# ADC.net
KiCad netlist of a schematic drawn in Altium Designer
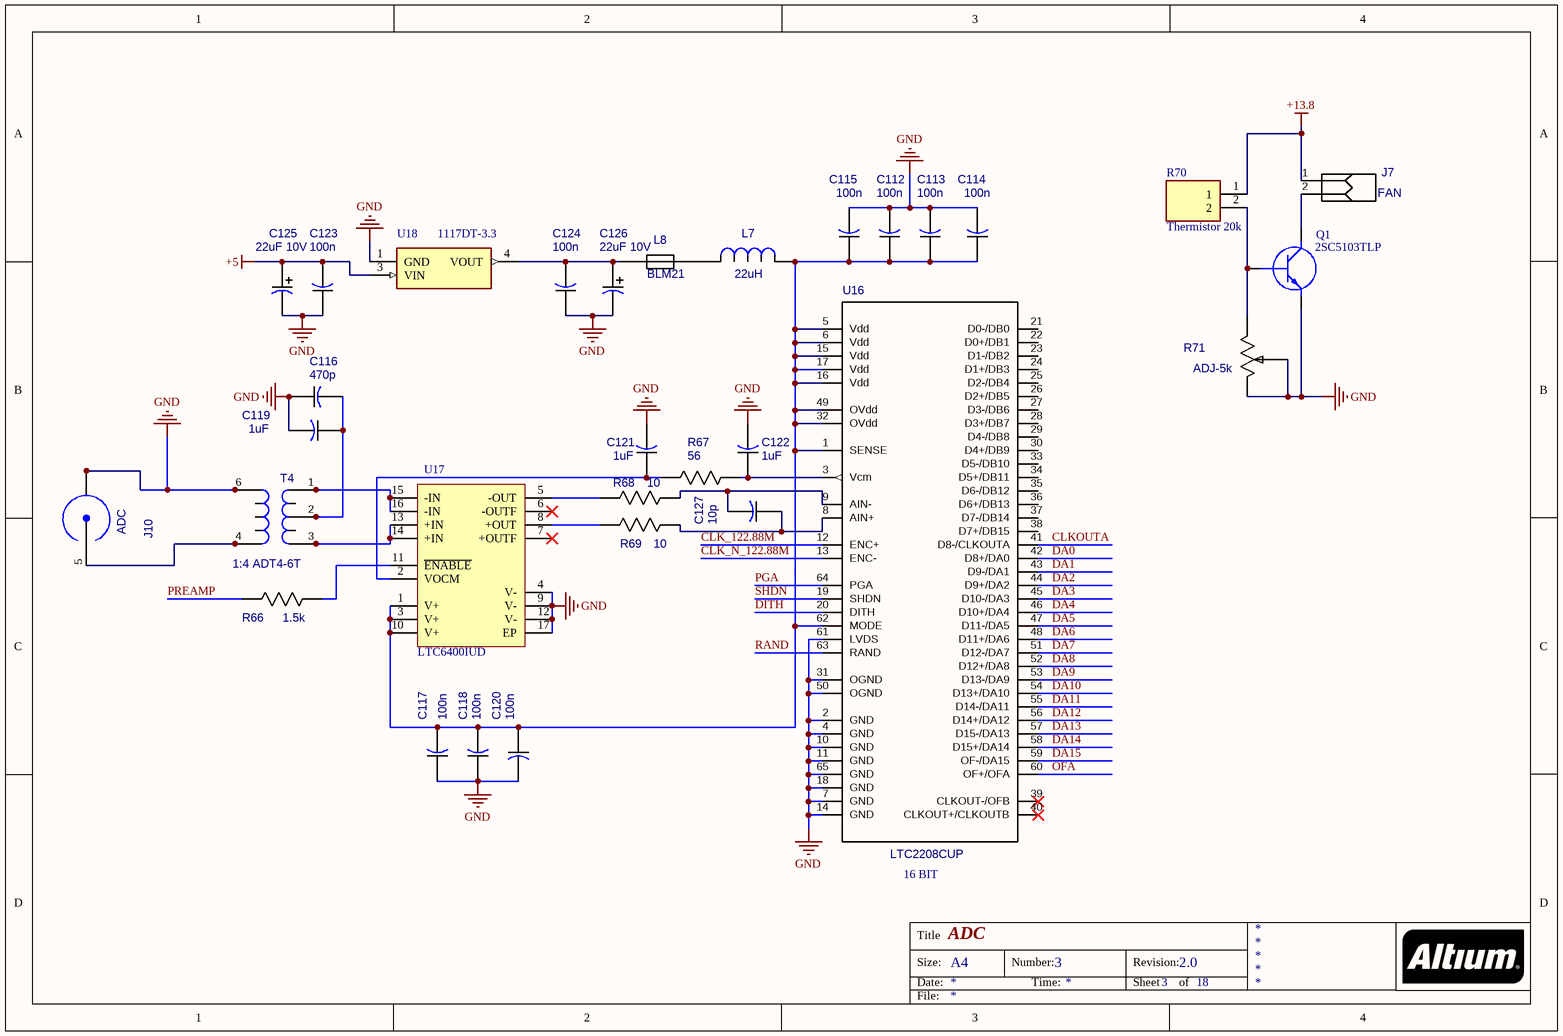
[diagram p0: ADC.SchDoc]

(export (version "E")
  (design (tool "Eeschema 10.0.6"))
  (components
    (comp (ref "C112")
      (value "100n")
      (footprint "CAP_0805")
      (description "CAP_0805")
      (libsource (lib "*") (part "CAP_0805"))
    )
    (comp (ref "C113")
      (value "100n")
      (footprint "CAP_0805")
      (description "CAP_0805")
      (libsource (lib "*") (part "CAP_0805"))
    )
    (comp (ref "C114")
      (value "100n")
      (footprint "CAP_0805")
      (description "CAP_0805")
      (libsource (lib "*") (part "CAP_0805"))
    )
    (comp (ref "C115")
      (value "100n")
      (footprint "CAP_0805")
      (description "CAP_0805")
      (libsource (lib "*") (part "CAP_0805"))
    )
    (comp (ref "C116")
      (value "470p")
      (footprint "CAP_0805")
      (description "CAP_0805")
      (libsource (lib "*") (part "CAP_0805"))
    )
    (comp (ref "C117")
      (value "100n")
      (footprint "CAP_0805")
      (description "CAP_0805")
      (libsource (lib "*") (part "CAP_0805"))
    )
    (comp (ref "C118")
      (value "100n")
      (footprint "CAP_0805")
      (description "CAP_0805")
      (libsource (lib "*") (part "CAP_0805"))
    )
    (comp (ref "C119")
      (value "1uF")
      (footprint "CAP_0805")
      (description "CAP_0805")
      (libsource (lib "*") (part "CAP_0805"))
    )
    (comp (ref "C120")
      (value "100n")
      (footprint "CAP_0805")
      (description "CAP_0805")
      (libsource (lib "*") (part "CAP_0805"))
    )
    (comp (ref "C121")
      (value "1uF")
      (footprint "CAP_0805")
      (description "CAP_0805")
      (libsource (lib "*") (part "CAP_0805"))
    )
    (comp (ref "C122")
      (value "1uF")
      (footprint "CAP_0805")
      (description "CAP_0805")
      (libsource (lib "*") (part "CAP_0805"))
    )
    (comp (ref "C123")
      (value "100n")
      (footprint "CAP_0805")
      (description "CAP_0805")
      (libsource (lib "*") (part "CAP_0805"))
    )
    (comp (ref "C124")
      (value "100n")
      (footprint "CAP_0805")
      (description "CAP_0805")
      (libsource (lib "*") (part "CAP_0805"))
    )
    (comp (ref "C125")
      (value "22uF 10V")
      (footprint "CAPAE_4.3x4.3h5.4")
      (description "CAPAE_4.3x4.3h5.4")
      (libsource (lib "MOTHERBOARD") (part "CAPAE_4.3x4.3h5.4"))
    )
    (comp (ref "C126")
      (value "22uF 10V")
      (footprint "CAPAE_4.3x4.3h5.4")
      (description "CAPAE_4.3x4.3h5.4")
      (libsource (lib "MOTHERBOARD") (part "CAPAE_4.3x4.3h5.4"))
    )
    (comp (ref "C127")
      (value "10p")
      (footprint "CAP_0805")
      (description "CAP_0805")
      (libsource (lib "*") (part "CAP_0805"))
    )
    (comp (ref "J7")
      (value "FAN")
      (footprint "51022-0200")
      (description "51022-0200")
      (libsource (lib "*") (part "51022-0200"))
    )
    (comp (ref "J10")
      (value "ADC")
      (footprint "31-5431")
      (description "SMA")
      (libsource (lib "RF-UNIT_1") (part "31-5431"))
    )
    (comp (ref "L7")
      (value "22uH")
      (footprint "IND_7x7")
      (description "IND_1206")
      (libsource (lib "*") (part "IND_1206"))
    )
    (comp (ref "L8")
      (value "BLM21")
      (footprint "CAP_0805")
      (libsource (lib "MOTHERBOARD_1") (part "IND_FERRITE_BEAD"))
    )
    (comp (ref "Q1")
      (value "2SC5103TLP")
      (footprint "SamacSys:2SC5103TLQ")
      (description "Transistor BJT NPN")
      (fields (field (name "MOUSER PART NUMBER") "755-2SC5103TLP"))
      (libsource (lib "*") (part "2SC5103TLP"))
    )
    (comp (ref "R66")
      (value "1.5k")
      (footprint "RES_0805")
      (description "RES_0805")
      (libsource (lib "") (part "RES_0805_1"))
    )
    (comp (ref "R67")
      (value "56")
      (footprint "RES_0805")
      (description "RES_0805")
      (libsource (lib "*") (part "RES_0805"))
    )
    (comp (ref "R68")
      (value "10")
      (footprint "RES_0603")
      (description "RES_0603")
      (libsource (lib "*") (part "RES_0603"))
    )
    (comp (ref "R69")
      (value "10")
      (footprint "RES_0603")
      (description "RES_0603")
      (libsource (lib "*") (part "RES_0603"))
    )
    (comp (ref "R70")
      (value "Thermistor 20k")
      (footprint "MF52A103F3950A1")
      (description "Thermistor")
      (fields (field (name "MANUFACTURER_PART_NUMBER") "MF52A103F3950(A1)"))
      (libsource (lib "*") (part "MF52A103F3950_A1_"))
    )
    (comp (ref "R71")
      (value "ADJ-5k")
      (footprint "306J")
      (description "306J")
      (libsource (lib "*") (part "306J"))
    )
    (comp (ref "T4")
      (value "1:4 ADT4-6T")
      (footprint "TRANSF_ACORE2")
      (description "Transformer")
      (libsource (lib "MOTHERBOARD_1") (part "TRANSF_ACORE2"))
    )
    (comp (ref "U16") (value "LTC2208CUP") (footprint "LTC2208CUP") (libsource (lib "*") (part "LTC2208CUP")))
    (comp (ref "U17")
      (value "LTC6400IUD")
      (footprint "LT-UD-16_N")
      (fields
        (field (name "MANUFACTURER") "Linear Technology")
        (field (name "LINEAR TECHNOLOGY PART NUMBER") "LTC6400-20")
        (field (name "PARTNUMBER") "LTC6400IUD-20#PBF")
      )
      (libsource (lib "Altium Content Vault") (part "LT-LTC640X-X-16"))
    )
    (comp (ref "U18")
      (value "1117DT-3.3")
      (footprint "SamacSys:TO228P991X238-3N")
      (description "LD1117DT33 DPAK")
      (fields
        (field (name "MANUFACTURER_PART_NUMBER") "LM1117DT-ADJ")
        (field (name "MOUSER PART NUMBER") "926-LM1117DT-ADJ")
      )
      (libsource (lib "*") (part "LM1117DT-ADJ"))
    )
  )
  (nets
    (net (code "1") (name "+5") (class "Default")
      (node (ref "C123") (pin "2") (pinfunction "2_2") (pintype "passive"))
      (node (ref "C125") (pin "1") (pinfunction "PLUS_1") (pintype "passive"))
      (node (ref "U18") (pin "3") (pinfunction "VIN_3") (pintype "input"))
    )
    (net (code "2") (name "+13.8") (class "Default")
      (node (ref "J7") (pin "1") (pinfunction "1_1") (pintype "passive"))
      (node (ref "R70") (pin "1") (pinfunction "1_1") (pintype "passive"))
    )
    (net (code "3") (name "/CLKOUTA") (class "Default")
      (node (ref "U16") (pin "41") (pinfunction "D8-/CLKOUTA_41") (pintype "passive"))
    )
    (net (code "4") (name "/CLK_122.88M") (class "Default")
      (node (ref "U16") (pin "12") (pinfunction "ENC+_12") (pintype "passive"))
    )
    (net (code "5") (name "/CLK_N_122.88M") (class "Default")
      (node (ref "U16") (pin "13") (pinfunction "ENC-_13") (pintype "passive"))
    )
    (net (code "6") (name "/DA0") (class "Default")
      (node (ref "U16") (pin "42") (pinfunction "D8+/DA0_42") (pintype "passive"))
    )
    (net (code "7") (name "/DA1") (class "Default")
      (node (ref "U16") (pin "43") (pinfunction "D9-/DA1_43") (pintype "passive"))
    )
    (net (code "8") (name "/DA2") (class "Default")
      (node (ref "U16") (pin "44") (pinfunction "D9+/DA2_44") (pintype "passive"))
    )
    (net (code "9") (name "/DA3") (class "Default")
      (node (ref "U16") (pin "45") (pinfunction "D10-/DA3_45") (pintype "passive"))
    )
    (net (code "10") (name "/DA4") (class "Default")
      (node (ref "U16") (pin "46") (pinfunction "D10+/DA4_46") (pintype "passive"))
    )
    (net (code "11") (name "/DA5") (class "Default")
      (node (ref "U16") (pin "47") (pinfunction "D11-/DA5_47") (pintype "passive"))
    )
    (net (code "12") (name "/DA6") (class "Default")
      (node (ref "U16") (pin "48") (pinfunction "D11+/DA6_48") (pintype "passive"))
    )
    (net (code "13") (name "/DA7") (class "Default")
      (node (ref "U16") (pin "51") (pinfunction "D12-/DA7_51") (pintype "passive"))
    )
    (net (code "14") (name "/DA8") (class "Default")
      (node (ref "U16") (pin "52") (pinfunction "D12+/DA8_52") (pintype "passive"))
    )
    (net (code "15") (name "/DA9") (class "Default")
      (node (ref "U16") (pin "53") (pinfunction "D13-/DA9_53") (pintype "passive"))
    )
    (net (code "16") (name "/DA10") (class "Default")
      (node (ref "U16") (pin "54") (pinfunction "D13+/DA10_54") (pintype "passive"))
    )
    (net (code "17") (name "/DA11") (class "Default")
      (node (ref "U16") (pin "55") (pinfunction "D14-/DA11_55") (pintype "passive"))
    )
    (net (code "18") (name "/DA12") (class "Default")
      (node (ref "U16") (pin "56") (pinfunction "D14+/DA12_56") (pintype "passive"))
    )
    (net (code "19") (name "/DA13") (class "Default")
      (node (ref "U16") (pin "57") (pinfunction "D15-/DA13_57") (pintype "passive"))
    )
    (net (code "20") (name "/DA14") (class "Default")
      (node (ref "U16") (pin "58") (pinfunction "D15+/DA14_58") (pintype "passive"))
    )
    (net (code "21") (name "/DA15") (class "Default")
      (node (ref "U16") (pin "59") (pinfunction "OF-/DA15_59") (pintype "passive"))
    )
    (net (code "22") (name "/DITH") (class "Default")
      (node (ref "U16") (pin "20") (pinfunction "DITH_20") (pintype "passive"))
    )
    (net (code "23") (name "/OFA") (class "Default")
      (node (ref "U16") (pin "60") (pinfunction "OF+/OFA_60") (pintype "passive"))
    )
    (net (code "24") (name "/PGA") (class "Default")
      (node (ref "U16") (pin "64") (pinfunction "PGA_64") (pintype "passive"))
    )
    (net (code "25") (name "/PREAMP") (class "Default")
      (node (ref "R66") (pin "2") (pinfunction "1_2") (pintype "passive"))
    )
    (net (code "26") (name "/RAND") (class "Default")
      (node (ref "U16") (pin "63") (pinfunction "RAND_63") (pintype "passive"))
    )
    (net (code "27") (name "/SHDN") (class "Default")
      (node (ref "U16") (pin "19") (pinfunction "SHDN_19") (pintype "passive"))
    )
    (net (code "28") (name "GND") (class "Default")
      (node (ref "C112") (pin "2") (pinfunction "2_2") (pintype "passive"))
      (node (ref "C113") (pin "2") (pinfunction "2_2") (pintype "passive"))
      (node (ref "C114") (pin "2") (pinfunction "2_2") (pintype "passive"))
      (node (ref "C115") (pin "2") (pinfunction "2_2") (pintype "passive"))
      (node (ref "C116") (pin "1") (pinfunction "1_1") (pintype "passive"))
      (node (ref "C117") (pin "1") (pinfunction "1_1") (pintype "passive"))
      (node (ref "C118") (pin "1") (pinfunction "1_1") (pintype "passive"))
      (node (ref "C119") (pin "2") (pinfunction "2_2") (pintype "passive"))
      (node (ref "C120") (pin "2") (pinfunction "2_2") (pintype "passive"))
      (node (ref "C121") (pin "2") (pinfunction "2_2") (pintype "passive"))
      (node (ref "C122") (pin "2") (pinfunction "2_2") (pintype "passive"))
      (node (ref "C123") (pin "1") (pinfunction "1_1") (pintype "passive"))
      (node (ref "C124") (pin "1") (pinfunction "1_1") (pintype "passive"))
      (node (ref "C125") (pin "2") (pinfunction "MINUS_2") (pintype "passive"))
      (node (ref "C126") (pin "2") (pinfunction "MINUS_2") (pintype "passive"))
      (node (ref "J10") (pin "1") (pinfunction "GND_1") (pintype "passive"))
      (node (ref "J10") (pin "2") (pinfunction "GND_2") (pintype "passive"))
      (node (ref "J10") (pin "3") (pinfunction "GND_3") (pintype "passive"))
      (node (ref "J10") (pin "4") (pinfunction "GND_4") (pintype "passive"))
      (node (ref "Q1") (pin "3") (pinfunction "E_3") (pintype "passive"))
      (node (ref "R71") (pin "1") (pinfunction "CCW_1") (pintype "passive"))
      (node (ref "R71") (pin "2") (pinfunction "W_2") (pintype "passive"))
      (node (ref "T4") (pin "10") (pinfunction "0_10") (pintype "passive"))
      (node (ref "T4") (pin "6") (pinfunction "P2_6") (pintype "passive"))
      (node (ref "U16") (pin "10") (pinfunction "GND_10") (pintype "passive"))
      (node (ref "U16") (pin "11") (pinfunction "GND_11") (pintype "passive"))
      (node (ref "U16") (pin "14") (pinfunction "GND_14") (pintype "passive"))
      (node (ref "U16") (pin "18") (pinfunction "GND_18") (pintype "passive"))
      (node (ref "U16") (pin "2") (pinfunction "GND_2") (pintype "passive"))
      (node (ref "U16") (pin "31") (pinfunction "OGND_31") (pintype "passive"))
      (node (ref "U16") (pin "4") (pinfunction "GND_4") (pintype "passive"))
      (node (ref "U16") (pin "50") (pinfunction "OGND_50") (pintype "passive"))
      (node (ref "U16") (pin "61") (pinfunction "LVDS_61") (pintype "passive"))
      (node (ref "U16") (pin "65") (pinfunction "GND_65") (pintype "passive"))
      (node (ref "U16") (pin "7") (pinfunction "GND_7") (pintype "passive"))
      (node (ref "U17") (pin "12") (pinfunction "V-_12") (pintype "power_in"))
      (node (ref "U17") (pin "17") (pinfunction "EP_17") (pintype "power_in"))
      (node (ref "U17") (pin "4") (pinfunction "V-_4") (pintype "power_in"))
      (node (ref "U17") (pin "9") (pinfunction "V-_9") (pintype "power_in"))
      (node (ref "U18") (pin "1") (pinfunction "GND_1") (pintype "passive"))
    )
    (net (code "29") (name "Net-(C126-PLUS)") (class "Default")
      (node (ref "C124") (pin "2") (pinfunction "2_2") (pintype "passive"))
      (node (ref "C126") (pin "1") (pinfunction "PLUS_1") (pintype "passive"))
      (node (ref "L8") (pin "1") (pinfunction "1_1") (pintype "passive"))
      (node (ref "U18") (pin "4") (pinfunction "VOUT_4") (pintype "output"))
    )
    (net (code "30") (name "Net-(J10-CON)") (class "Default")
      (node (ref "J10") (pin "5") (pinfunction "CON_5") (pintype "passive"))
      (node (ref "T4") (pin "11") (pinfunction "0_11") (pintype "passive"))
      (node (ref "T4") (pin "4") (pinfunction "P1_4") (pintype "passive"))
    )
    (net (code "31") (name "Net-(L7-Pad1)") (class "Default")
      (node (ref "L7") (pin "1") (pinfunction "1_1") (pintype "passive"))
      (node (ref "L8") (pin "2") (pinfunction "2_2") (pintype "passive"))
    )
    (net (code "32") (name "Net-(Q1-B)") (class "Default")
      (node (ref "Q1") (pin "1") (pinfunction "B_1") (pintype "passive"))
      (node (ref "R70") (pin "2") (pinfunction "2_2") (pintype "passive"))
      (node (ref "R71") (pin "3") (pinfunction "CW_3") (pintype "passive"))
    )
    (net (code "33") (name "Net-(Q1-C)") (class "Default")
      (node (ref "J7") (pin "2") (pinfunction "2_2") (pintype "passive"))
      (node (ref "Q1") (pin "2") (pinfunction "C_2") (pintype "passive"))
    )
    (net (code "34") (name "Net-(R66-2)") (class "Default")
      (node (ref "R66") (pin "1") (pinfunction "2_1") (pintype "passive"))
      (node (ref "U17") (pin "11") (pinfunction "~{ENABLE}_11") (pintype "passive"))
    )
    (net (code "35") (name "Net-(T4-S1)") (class "Default")
      (node (ref "T4") (pin "3") (pinfunction "S1_3") (pintype "passive"))
      (node (ref "T4") (pin "9") (pinfunction "0_9") (pintype "passive"))
      (node (ref "U17") (pin "13") (pinfunction "+IN_13") (pintype "passive"))
      (node (ref "U17") (pin "14") (pinfunction "+IN_14") (pintype "passive"))
    )
    (net (code "36") (name "Net-(T4-S2)") (class "Default")
      (node (ref "C116") (pin "2") (pinfunction "2_2") (pintype "passive"))
      (node (ref "C119") (pin "1") (pinfunction "1_1") (pintype "passive"))
      (node (ref "T4") (pin "2") (pinfunction "S2_2") (pintype "passive"))
      (node (ref "T4") (pin "8") (pinfunction "0_8") (pintype "passive"))
    )
    (net (code "37") (name "Net-(T4-S3)") (class "Default")
      (node (ref "T4") (pin "1") (pinfunction "S3_1") (pintype "passive"))
      (node (ref "T4") (pin "7") (pinfunction "0_7") (pintype "passive"))
      (node (ref "U17") (pin "15") (pinfunction "-IN_15") (pintype "passive"))
      (node (ref "U17") (pin "16") (pinfunction "-IN_16") (pintype "passive"))
    )
    (net (code "38") (name "Net-(U16-AIN+)") (class "Default")
      (node (ref "C127") (pin "1") (pinfunction "1_1") (pintype "passive"))
      (node (ref "R69") (pin "2") (pinfunction "2_2") (pintype "passive"))
      (node (ref "U16") (pin "8") (pinfunction "AIN+_8") (pintype "passive"))
    )
    (net (code "39") (name "Net-(U16-AIN-)") (class "Default")
      (node (ref "C127") (pin "2") (pinfunction "2_2") (pintype "passive"))
      (node (ref "R68") (pin "2") (pinfunction "2_2") (pintype "passive"))
      (node (ref "U16") (pin "9") (pinfunction "AIN-_9") (pintype "passive"))
    )
    (net (code "40") (name "Net-(U16-MODE)") (class "Default")
      (node (ref "C112") (pin "1") (pinfunction "1_1") (pintype "passive"))
      (node (ref "C113") (pin "1") (pinfunction "1_1") (pintype "passive"))
      (node (ref "C114") (pin "1") (pinfunction "1_1") (pintype "passive"))
      (node (ref "C115") (pin "1") (pinfunction "1_1") (pintype "passive"))
      (node (ref "C117") (pin "2") (pinfunction "2_2") (pintype "passive"))
      (node (ref "C118") (pin "2") (pinfunction "2_2") (pintype "passive"))
      (node (ref "C120") (pin "1") (pinfunction "1_1") (pintype "passive"))
      (node (ref "L7") (pin "2") (pinfunction "2_2") (pintype "passive"))
      (node (ref "U16") (pin "1") (pinfunction "SENSE_1") (pintype "passive"))
      (node (ref "U16") (pin "15") (pinfunction "Vdd_15") (pintype "passive"))
      (node (ref "U16") (pin "16") (pinfunction "Vdd_16") (pintype "passive"))
      (node (ref "U16") (pin "17") (pinfunction "Vdd_17") (pintype "passive"))
      (node (ref "U16") (pin "32") (pinfunction "OVdd_32") (pintype "passive"))
      (node (ref "U16") (pin "49") (pinfunction "OVdd_49") (pintype "passive"))
      (node (ref "U16") (pin "5") (pinfunction "Vdd_5") (pintype "passive"))
      (node (ref "U16") (pin "6") (pinfunction "Vdd_6") (pintype "passive"))
      (node (ref "U16") (pin "62") (pinfunction "MODE_62") (pintype "passive"))
      (node (ref "U17") (pin "1") (pinfunction "V+_1") (pintype "power_in"))
      (node (ref "U17") (pin "10") (pinfunction "V+_10") (pintype "power_in"))
      (node (ref "U17") (pin "3") (pinfunction "V+_3") (pintype "power_in"))
    )
    (net (code "41") (name "Net-(U16-Vcm)") (class "Default")
      (node (ref "C122") (pin "1") (pinfunction "1_1") (pintype "passive"))
      (node (ref "R67") (pin "2") (pinfunction "2_2") (pintype "passive"))
      (node (ref "U16") (pin "3") (pinfunction "Vcm_3") (pintype "output"))
    )
    (net (code "42") (name "Net-(U17-+OUT)") (class "Default")
      (node (ref "R69") (pin "1") (pinfunction "1_1") (pintype "passive"))
      (node (ref "U17") (pin "8") (pinfunction "+OUT_8") (pintype "passive"))
    )
    (net (code "43") (name "Net-(U17--OUT)") (class "Default")
      (node (ref "R68") (pin "1") (pinfunction "1_1") (pintype "passive"))
      (node (ref "U17") (pin "5") (pinfunction "-OUT_5") (pintype "passive"))
    )
    (net (code "44") (name "Net-(U17-VOCM)") (class "Default")
      (node (ref "C121") (pin "1") (pinfunction "1_1") (pintype "passive"))
      (node (ref "R67") (pin "1") (pinfunction "1_1") (pintype "passive"))
      (node (ref "U17") (pin "2") (pinfunction "VOCM_2") (pintype "passive"))
    )
    (net (code "45") (name "unconnected-(U16-CLKOUT+{slash}CLKOUTB-Pad40)") (class "Default")
      (node (ref "U16") (pin "40") (pinfunction "CLKOUT+/CLKOUTB_40") (pintype "passive+no_connect"))
    )
    (net (code "46") (name "unconnected-(U16-CLKOUT-{slash}OFB-Pad39)") (class "Default")
      (node (ref "U16") (pin "39") (pinfunction "CLKOUT-/OFB_39") (pintype "passive+no_connect"))
    )
    (net (code "47") (name "unconnected-(U16-D0+{slash}DB1-Pad22)") (class "Default")
      (node (ref "U16") (pin "22") (pinfunction "D0+/DB1_22") (pintype "passive"))
    )
    (net (code "48") (name "unconnected-(U16-D0-{slash}DB0-Pad21)") (class "Default")
      (node (ref "U16") (pin "21") (pinfunction "D0-/DB0_21") (pintype "passive"))
    )
    (net (code "49") (name "unconnected-(U16-D1+{slash}DB3-Pad24)") (class "Default")
      (node (ref "U16") (pin "24") (pinfunction "D1+/DB3_24") (pintype "passive"))
    )
    (net (code "50") (name "unconnected-(U16-D1-{slash}DB2-Pad23)") (class "Default")
      (node (ref "U16") (pin "23") (pinfunction "D1-/DB2_23") (pintype "passive"))
    )
    (net (code "51") (name "unconnected-(U16-D2+{slash}DB5-Pad26)") (class "Default")
      (node (ref "U16") (pin "26") (pinfunction "D2+/DB5_26") (pintype "passive"))
    )
    (net (code "52") (name "unconnected-(U16-D2-{slash}DB4-Pad25)") (class "Default")
      (node (ref "U16") (pin "25") (pinfunction "D2-/DB4_25") (pintype "passive"))
    )
    (net (code "53") (name "unconnected-(U16-D3+{slash}DB7-Pad28)") (class "Default")
      (node (ref "U16") (pin "28") (pinfunction "D3+/DB7_28") (pintype "passive"))
    )
    (net (code "54") (name "unconnected-(U16-D3-{slash}DB6-Pad27)") (class "Default")
      (node (ref "U16") (pin "27") (pinfunction "D3-/DB6_27") (pintype "passive"))
    )
    (net (code "55") (name "unconnected-(U16-D4+{slash}DB9-Pad30)") (class "Default")
      (node (ref "U16") (pin "30") (pinfunction "D4+/DB9_30") (pintype "passive"))
    )
    (net (code "56") (name "unconnected-(U16-D4-{slash}DB8-Pad29)") (class "Default")
      (node (ref "U16") (pin "29") (pinfunction "D4-/DB8_29") (pintype "passive"))
    )
    (net (code "57") (name "unconnected-(U16-D5+{slash}DB11-Pad34)") (class "Default")
      (node (ref "U16") (pin "34") (pinfunction "D5+/DB11_34") (pintype "passive"))
    )
    (net (code "58") (name "unconnected-(U16-D5-{slash}DB10-Pad33)") (class "Default")
      (node (ref "U16") (pin "33") (pinfunction "D5-/DB10_33") (pintype "passive"))
    )
    (net (code "59") (name "unconnected-(U16-D6+{slash}DB13-Pad36)") (class "Default")
      (node (ref "U16") (pin "36") (pinfunction "D6+/DB13_36") (pintype "passive"))
    )
    (net (code "60") (name "unconnected-(U16-D6-{slash}DB12-Pad35)") (class "Default")
      (node (ref "U16") (pin "35") (pinfunction "D6-/DB12_35") (pintype "passive"))
    )
    (net (code "61") (name "unconnected-(U16-D7+{slash}DB15-Pad38)") (class "Default")
      (node (ref "U16") (pin "38") (pinfunction "D7+/DB15_38") (pintype "passive"))
    )
    (net (code "62") (name "unconnected-(U16-D7-{slash}DB14-Pad37)") (class "Default")
      (node (ref "U16") (pin "37") (pinfunction "D7-/DB14_37") (pintype "passive"))
    )
    (net (code "63") (name "unconnected-(U17-+OUTF-Pad7)") (class "Default")
      (node (ref "U17") (pin "7") (pinfunction "+OUTF_7") (pintype "passive+no_connect"))
    )
    (net (code "64") (name "unconnected-(U17--OUTF-Pad6)") (class "Default")
      (node (ref "U17") (pin "6") (pinfunction "-OUTF_6") (pintype "passive+no_connect"))
    )
  )
)
